# ProProject_GuudBox.net
KiCad netlist of a schematic drawn in EasyEDA Pro
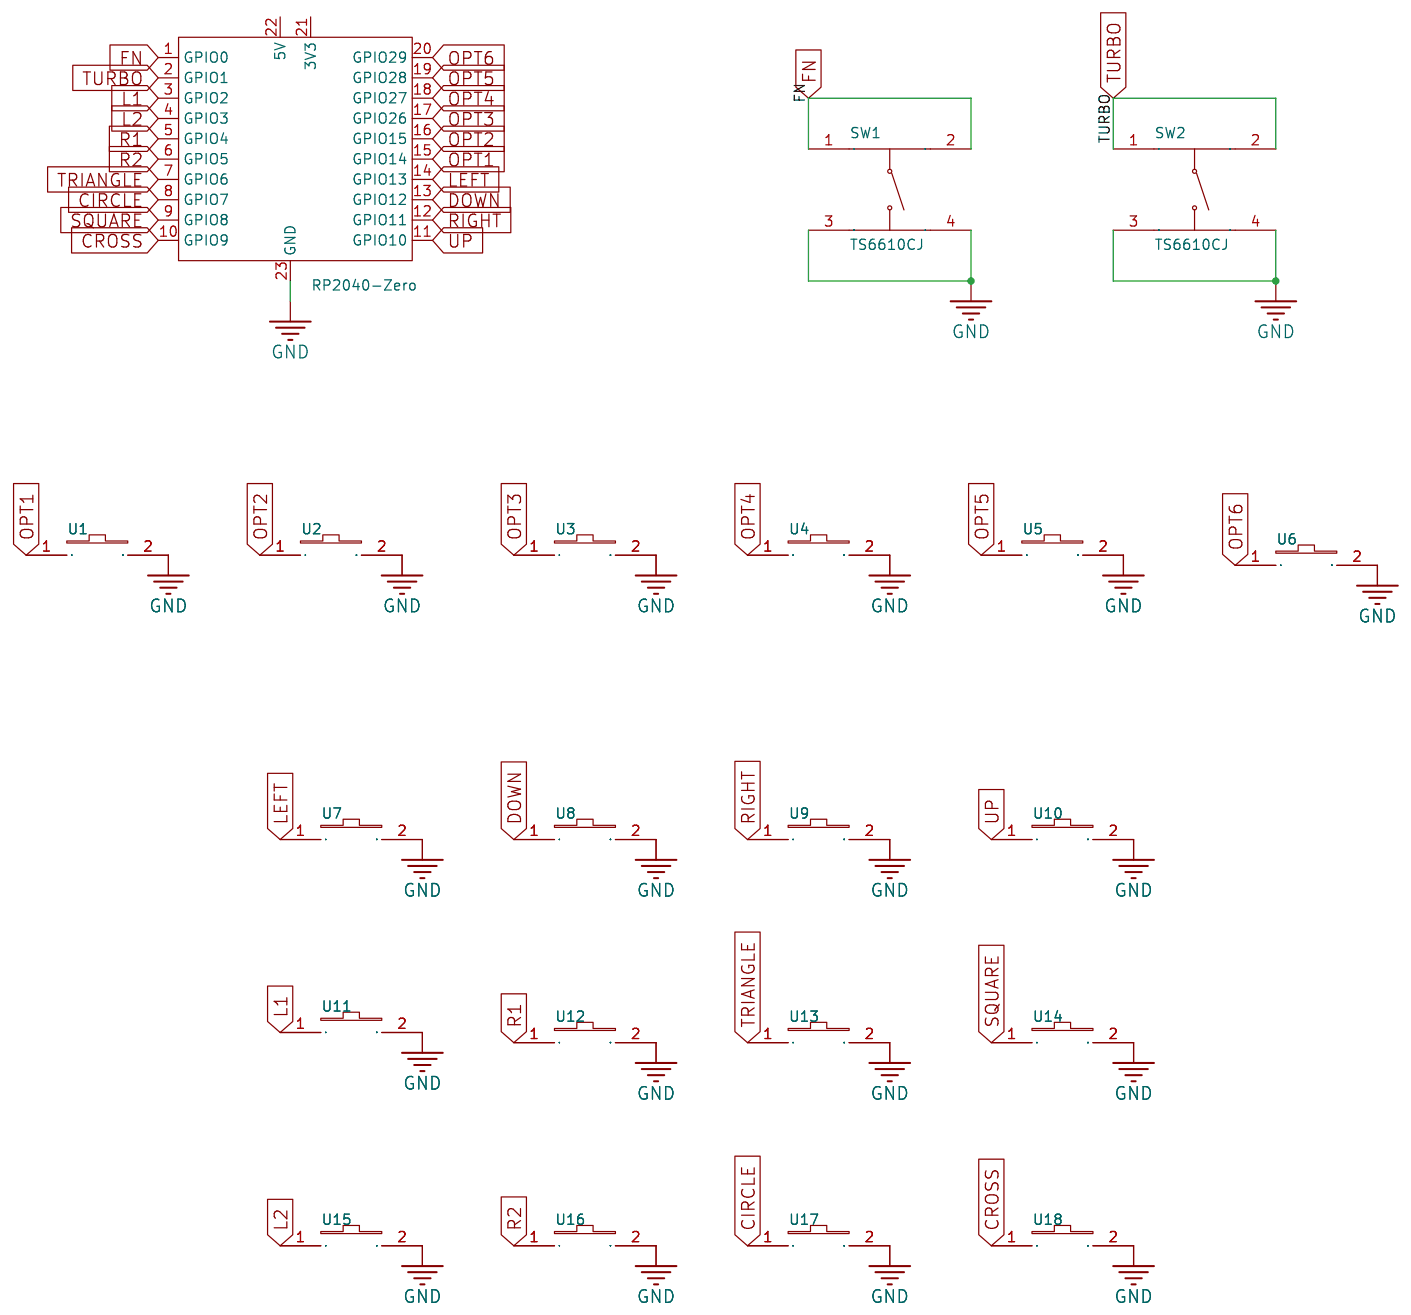
[diagram p0: schematic sheet]

(export (version "E")
  (design (tool "Eeschema 10.0.6"))
  (components
    (comp (ref "RP2040-Zero")
      (value "RP2040-Zero_RP2040-Zero")
      (footprint "easyedapro:WaveShare RP2040-Zero near_edge_bottom_side")
      (libsource (lib "easyedapro") (part "WaveShare RP2040-Zero"))
    )
    (comp (ref "SW1")
      (value "TS6610CJ")
      (footprint "easyedapro:SW-TH_4P-L6.0-W6.0-P4.50-LS6.5")
      (description "触点电流:50mA;额定电压(DC):12V;绝缘电阻:100MΩ;电路结构:单刀单掷;安装方式:直插;作用力:250gf@±30gf;机械寿命:8万次;带支架:否;")
      (fields (field (name "Manufacturer") "SHOU HAN(首韩)"))
      (libsource (lib "easyedapro") (part "TS6610CJ"))
    )
    (comp (ref "SW2")
      (value "TS6610CJ")
      (footprint "easyedapro:SW-TH_4P-L6.0-W6.0-P4.50-LS6.5")
      (description "触点电流:50mA;额定电压(DC):12V;绝缘电阻:100MΩ;电路结构:单刀单掷;安装方式:直插;作用力:250gf@±30gf;机械寿命:8万次;带支架:否;")
      (fields (field (name "Manufacturer") "SHOU HAN(首韩)"))
      (libsource (lib "easyedapro") (part "TS6610CJ"))
    )
    (comp (ref "U1")
      (value "~")
      (footprint "easyedapro:GATERON low profile hot-swap flip_routing")
      (libsource (lib "easyedapro") (part "GATERON low profile hot-swap"))
    )
    (comp (ref "U2")
      (value "~")
      (footprint "easyedapro:GATERON low profile hot-swap flip_routing")
      (libsource (lib "easyedapro") (part "GATERON low profile hot-swap"))
    )
    (comp (ref "U3")
      (value "~")
      (footprint "easyedapro:GATERON low profile hot-swap flip_routing")
      (libsource (lib "easyedapro") (part "GATERON low profile hot-swap"))
    )
    (comp (ref "U4")
      (value "~")
      (footprint "easyedapro:GATERON low profile hot-swap flip_routing")
      (libsource (lib "easyedapro") (part "GATERON low profile hot-swap"))
    )
    (comp (ref "U5")
      (value "~")
      (footprint "easyedapro:GATERON low profile hot-swap flip_routing")
      (libsource (lib "easyedapro") (part "GATERON low profile hot-swap"))
    )
    (comp (ref "U6")
      (value "~")
      (footprint "easyedapro:GATERON low profile hot-swap flip_routing")
      (libsource (lib "easyedapro") (part "GATERON low profile hot-swap"))
    )
    (comp (ref "U7")
      (value "~")
      (footprint "easyedapro:GATERON low profile hot-swap flip_routing")
      (libsource (lib "easyedapro") (part "GATERON low profile hot-swap"))
    )
    (comp (ref "U8")
      (value "~")
      (footprint "easyedapro:GATERON low profile hot-swap flip_routing")
      (libsource (lib "easyedapro") (part "GATERON low profile hot-swap"))
    )
    (comp (ref "U9")
      (value "~")
      (footprint "easyedapro:GATERON low profile hot-swap flip_routing")
      (libsource (lib "easyedapro") (part "GATERON low profile hot-swap"))
    )
    (comp (ref "U10")
      (value "~")
      (footprint "easyedapro:GATERON low profile hot-swap flip_routing")
      (libsource (lib "easyedapro") (part "GATERON low profile hot-swap"))
    )
    (comp (ref "U11")
      (value "~")
      (footprint "easyedapro:GATERON low profile hot-swap flip_routing")
      (libsource (lib "easyedapro") (part "GATERON low profile hot-swap"))
    )
    (comp (ref "U12")
      (value "~")
      (footprint "easyedapro:GATERON low profile hot-swap flip_routing")
      (libsource (lib "easyedapro") (part "GATERON low profile hot-swap"))
    )
    (comp (ref "U13")
      (value "~")
      (footprint "easyedapro:GATERON low profile hot-swap flip_routing")
      (libsource (lib "easyedapro") (part "GATERON low profile hot-swap"))
    )
    (comp (ref "U14")
      (value "~")
      (footprint "easyedapro:GATERON low profile hot-swap flip_routing")
      (libsource (lib "easyedapro") (part "GATERON low profile hot-swap"))
    )
    (comp (ref "U15")
      (value "~")
      (footprint "easyedapro:GATERON low profile hot-swap flip_routing")
      (libsource (lib "easyedapro") (part "GATERON low profile hot-swap"))
    )
    (comp (ref "U16")
      (value "~")
      (footprint "easyedapro:GATERON low profile hot-swap flip_routing")
      (libsource (lib "easyedapro") (part "GATERON low profile hot-swap"))
    )
    (comp (ref "U17")
      (value "~")
      (footprint "easyedapro:GATERON low profile hot-swap flip_routing")
      (libsource (lib "easyedapro") (part "GATERON low profile hot-swap"))
    )
    (comp (ref "U18")
      (value "~")
      (footprint "easyedapro:GATERON low profile hot-swap flip_routing")
      (libsource (lib "easyedapro") (part "GATERON low profile hot-swap"))
    )
  )
  (nets
    (net (code "1") (name "CIRCLE") (class "Default")
      (node (ref "RP2040-Zero") (pin "8") (pinfunction "GPIO7_8") (pintype "bidirectional"))
      (node (ref "U17") (pin "1") (pinfunction "1_1") (pintype "input"))
    )
    (net (code "2") (name "CROSS") (class "Default")
      (node (ref "RP2040-Zero") (pin "10") (pinfunction "GPIO9_10") (pintype "bidirectional"))
      (node (ref "U18") (pin "1") (pinfunction "1_1") (pintype "input"))
    )
    (net (code "3") (name "DOWN") (class "Default")
      (node (ref "RP2040-Zero") (pin "13") (pinfunction "GPIO12_13") (pintype "bidirectional"))
      (node (ref "U8") (pin "1") (pinfunction "1_1") (pintype "input"))
    )
    (net (code "4") (name "FN") (class "Default")
      (node (ref "RP2040-Zero") (pin "1") (pinfunction "GPIO0_1") (pintype "bidirectional"))
      (node (ref "SW1") (pin "1") (pinfunction "A_1") (pintype "input"))
      (node (ref "SW1") (pin "2") (pinfunction "B_2") (pintype "input"))
    )
    (net (code "5") (name "GND") (class "Default")
      (node (ref "RP2040-Zero") (pin "23") (pinfunction "GND_23") (pintype "input"))
      (node (ref "SW1") (pin "3") (pinfunction "C_3") (pintype "input"))
      (node (ref "SW1") (pin "4") (pinfunction "D_4") (pintype "input"))
      (node (ref "SW2") (pin "3") (pinfunction "C_3") (pintype "input"))
      (node (ref "SW2") (pin "4") (pinfunction "D_4") (pintype "input"))
      (node (ref "U1") (pin "2") (pinfunction "2_2") (pintype "input"))
      (node (ref "U10") (pin "2") (pinfunction "2_2") (pintype "input"))
      (node (ref "U11") (pin "2") (pinfunction "2_2") (pintype "input"))
      (node (ref "U12") (pin "2") (pinfunction "2_2") (pintype "input"))
      (node (ref "U13") (pin "2") (pinfunction "2_2") (pintype "input"))
      (node (ref "U14") (pin "2") (pinfunction "2_2") (pintype "input"))
      (node (ref "U15") (pin "2") (pinfunction "2_2") (pintype "input"))
      (node (ref "U16") (pin "2") (pinfunction "2_2") (pintype "input"))
      (node (ref "U17") (pin "2") (pinfunction "2_2") (pintype "input"))
      (node (ref "U18") (pin "2") (pinfunction "2_2") (pintype "input"))
      (node (ref "U2") (pin "2") (pinfunction "2_2") (pintype "input"))
      (node (ref "U3") (pin "2") (pinfunction "2_2") (pintype "input"))
      (node (ref "U4") (pin "2") (pinfunction "2_2") (pintype "input"))
      (node (ref "U5") (pin "2") (pinfunction "2_2") (pintype "input"))
      (node (ref "U6") (pin "2") (pinfunction "2_2") (pintype "input"))
      (node (ref "U7") (pin "2") (pinfunction "2_2") (pintype "input"))
      (node (ref "U8") (pin "2") (pinfunction "2_2") (pintype "input"))
      (node (ref "U9") (pin "2") (pinfunction "2_2") (pintype "input"))
    )
    (net (code "6") (name "L1") (class "Default")
      (node (ref "RP2040-Zero") (pin "3") (pinfunction "GPIO2_3") (pintype "bidirectional"))
      (node (ref "U11") (pin "1") (pinfunction "1_1") (pintype "input"))
    )
    (net (code "7") (name "L2") (class "Default")
      (node (ref "RP2040-Zero") (pin "4") (pinfunction "GPIO3_4") (pintype "bidirectional"))
      (node (ref "U15") (pin "1") (pinfunction "1_1") (pintype "input"))
    )
    (net (code "8") (name "LEFT") (class "Default")
      (node (ref "RP2040-Zero") (pin "14") (pinfunction "GPIO13_14") (pintype "bidirectional"))
      (node (ref "U7") (pin "1") (pinfunction "1_1") (pintype "input"))
    )
    (net (code "9") (name "OPT1") (class "Default")
      (node (ref "RP2040-Zero") (pin "15") (pinfunction "GPIO14_15") (pintype "bidirectional"))
      (node (ref "U1") (pin "1") (pinfunction "1_1") (pintype "input"))
    )
    (net (code "10") (name "OPT2") (class "Default")
      (node (ref "RP2040-Zero") (pin "16") (pinfunction "GPIO15_16") (pintype "bidirectional"))
      (node (ref "U2") (pin "1") (pinfunction "1_1") (pintype "input"))
    )
    (net (code "11") (name "OPT3") (class "Default")
      (node (ref "RP2040-Zero") (pin "17") (pinfunction "GPIO26_17") (pintype "bidirectional"))
      (node (ref "U3") (pin "1") (pinfunction "1_1") (pintype "input"))
    )
    (net (code "12") (name "OPT4") (class "Default")
      (node (ref "RP2040-Zero") (pin "18") (pinfunction "GPIO27_18") (pintype "bidirectional"))
      (node (ref "U4") (pin "1") (pinfunction "1_1") (pintype "input"))
    )
    (net (code "13") (name "OPT5") (class "Default")
      (node (ref "RP2040-Zero") (pin "19") (pinfunction "GPIO28_19") (pintype "bidirectional"))
      (node (ref "U5") (pin "1") (pinfunction "1_1") (pintype "input"))
    )
    (net (code "14") (name "OPT6") (class "Default")
      (node (ref "RP2040-Zero") (pin "20") (pinfunction "GPIO29_20") (pintype "bidirectional"))
      (node (ref "U6") (pin "1") (pinfunction "1_1") (pintype "input"))
    )
    (net (code "15") (name "R1") (class "Default")
      (node (ref "RP2040-Zero") (pin "5") (pinfunction "GPIO4_5") (pintype "bidirectional"))
      (node (ref "U12") (pin "1") (pinfunction "1_1") (pintype "input"))
    )
    (net (code "16") (name "R2") (class "Default")
      (node (ref "RP2040-Zero") (pin "6") (pinfunction "GPIO5_6") (pintype "bidirectional"))
      (node (ref "U16") (pin "1") (pinfunction "1_1") (pintype "input"))
    )
    (net (code "17") (name "RIGHT") (class "Default")
      (node (ref "RP2040-Zero") (pin "12") (pinfunction "GPIO11_12") (pintype "bidirectional"))
      (node (ref "U9") (pin "1") (pinfunction "1_1") (pintype "input"))
    )
    (net (code "18") (name "SQUARE") (class "Default")
      (node (ref "RP2040-Zero") (pin "9") (pinfunction "GPIO8_9") (pintype "bidirectional"))
      (node (ref "U14") (pin "1") (pinfunction "1_1") (pintype "input"))
    )
    (net (code "19") (name "TRIANGLE") (class "Default")
      (node (ref "RP2040-Zero") (pin "7") (pinfunction "GPIO6_7") (pintype "bidirectional"))
      (node (ref "U13") (pin "1") (pinfunction "1_1") (pintype "input"))
    )
    (net (code "20") (name "TURBO") (class "Default")
      (node (ref "RP2040-Zero") (pin "2") (pinfunction "GPIO1_2") (pintype "bidirectional"))
      (node (ref "SW2") (pin "1") (pinfunction "A_1") (pintype "input"))
      (node (ref "SW2") (pin "2") (pinfunction "B_2") (pintype "input"))
    )
    (net (code "21") (name "UP") (class "Default")
      (node (ref "RP2040-Zero") (pin "11") (pinfunction "GPIO10_11") (pintype "bidirectional"))
      (node (ref "U10") (pin "1") (pinfunction "1_1") (pintype "input"))
    )
    (net (code "22") (name "unconnected-(RP2040-Zero-3V3-Pad21)") (class "Default")
      (node (ref "RP2040-Zero") (pin "21") (pinfunction "3V3_21") (pintype "input"))
    )
    (net (code "23") (name "unconnected-(RP2040-Zero-5V-Pad22)") (class "Default")
      (node (ref "RP2040-Zero") (pin "22") (pinfunction "5V_22") (pintype "input"))
    )
  )
)
